# AlimTeleinfoMySensors.net
KiCad netlist of a schematic drawn in EAGLE
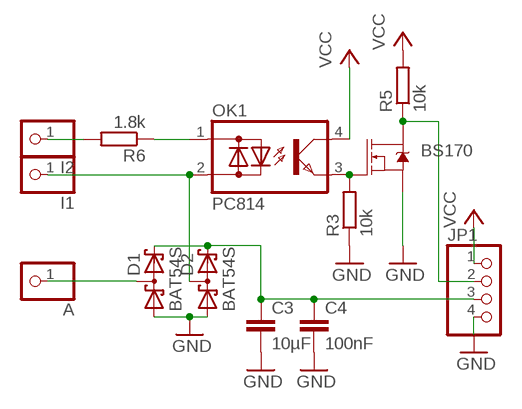
[diagram p0: schematic, sheet 1]

(export (version "E")
  (design (tool "Eeschema 10.0.6"))
  (components
    (comp (ref "A")
      (value "PINHD-1X1")
      (footprint "eagle-import:1X01")
      (libsource (lib "eagle-import") (part "PINHD-1X1"))
    )
    (comp (ref "BS170")
      (value "MOSFET-NCH-BSS138")
      (footprint "eagle-import:SOT23-3")
      (libsource (lib "eagle-import") (part "MOSFET-NCH-BSS138"))
    )
    (comp (ref "C3")
      (value "10µF")
      (footprint "eagle-import:C1210")
      (libsource (lib "eagle-import") (part "C-EUC1210"))
    )
    (comp (ref "C4")
      (value "100nF")
      (footprint "eagle-import:C1206")
      (libsource (lib "eagle-import") (part "C-EUC1206"))
    )
    (comp (ref "D1")
      (value "BAT54S")
      (footprint "eagle-import:SOT23")
      (libsource (lib "eagle-import") (part "BAT54S"))
    )
    (comp (ref "D2")
      (value "BAT54S")
      (footprint "eagle-import:SOT23")
      (libsource (lib "eagle-import") (part "BAT54S"))
    )
    (comp (ref "I1")
      (value "PINHD-1X1")
      (footprint "eagle-import:1X01")
      (libsource (lib "eagle-import") (part "PINHD-1X1"))
    )
    (comp (ref "I2")
      (value "PINHD-1X1")
      (footprint "eagle-import:1X01")
      (libsource (lib "eagle-import") (part "PINHD-1X1"))
    )
    (comp (ref "JP1")
      (value "PINHD-1X4")
      (footprint "eagle-import:1X04")
      (libsource (lib "eagle-import") (part "PINHD-1X4"))
    )
    (comp (ref "OK1")
      (value "PC814")
      (footprint "eagle-import:DIL04")
      (libsource (lib "eagle-import") (part "PC814"))
    )
    (comp (ref "R3")
      (value "10k")
      (footprint "eagle-import:M1206")
      (libsource (lib "eagle-import") (part "R-EU_M1206"))
    )
    (comp (ref "R5")
      (value "10k")
      (footprint "eagle-import:M1206")
      (libsource (lib "eagle-import") (part "R-EU_M1206"))
    )
    (comp (ref "R6")
      (value "1.8k")
      (footprint "eagle-import:M1206")
      (libsource (lib "eagle-import") (part "R-EU_M1206"))
    )
  )
  (nets
    (net (code "1") (name "GND") (class "Default")
      (node (ref "BS170") (pin "2") (pinfunction "S_2") (pintype "bidirectional"))
      (node (ref "C3") (pin "2") (pinfunction "2_2") (pintype "passive"))
      (node (ref "C4") (pin "2") (pinfunction "2_2") (pintype "passive"))
      (node (ref "D1") (pin "1") (pinfunction "A1_1") (pintype "passive"))
      (node (ref "D2") (pin "1") (pinfunction "A1_1") (pintype "passive"))
      (node (ref "JP1") (pin "4") (pinfunction "4_4") (pintype "passive"))
      (node (ref "R3") (pin "1") (pinfunction "1_1") (pintype "passive"))
    )
    (net (code "2") (name "Net-(BS170-D)") (class "Default")
      (node (ref "BS170") (pin "3") (pinfunction "D_3") (pintype "bidirectional"))
      (node (ref "JP1") (pin "2") (pinfunction "2_2") (pintype "passive"))
      (node (ref "R5") (pin "1") (pinfunction "1_1") (pintype "passive"))
    )
    (net (code "3") (name "Net-(BS170-G)") (class "Default")
      (node (ref "BS170") (pin "1") (pinfunction "G_1") (pintype "bidirectional"))
      (node (ref "OK1") (pin "3") (pinfunction "E_3") (pintype "passive"))
      (node (ref "R3") (pin "2") (pinfunction "2_2") (pintype "passive"))
    )
    (net (code "4") (name "Net-(D1-C1A2)") (class "Default")
      (node (ref "A") (pin "1") (pinfunction "1_1") (pintype "passive"))
      (node (ref "D1") (pin "3") (pinfunction "C1A2_3") (pintype "passive"))
    )
    (net (code "5") (name "Net-(D1-C2)") (class "Default")
      (node (ref "C3") (pin "1") (pinfunction "1_1") (pintype "passive"))
      (node (ref "C4") (pin "1") (pinfunction "1_1") (pintype "passive"))
      (node (ref "D1") (pin "2") (pinfunction "C2_2") (pintype "passive"))
      (node (ref "D2") (pin "2") (pinfunction "C2_2") (pintype "passive"))
      (node (ref "JP1") (pin "3") (pinfunction "3_3") (pintype "passive"))
    )
    (net (code "6") (name "Net-(D2-C1A2)") (class "Default")
      (node (ref "D2") (pin "3") (pinfunction "C1A2_3") (pintype "passive"))
      (node (ref "I1") (pin "1") (pinfunction "1_1") (pintype "passive"))
      (node (ref "OK1") (pin "2") (pinfunction "AC2_2") (pintype "passive"))
    )
    (net (code "7") (name "Net-(I2-Pad1)") (class "Default")
      (node (ref "I2") (pin "1") (pinfunction "1_1") (pintype "passive"))
      (node (ref "R6") (pin "2") (pinfunction "2_2") (pintype "passive"))
    )
    (net (code "8") (name "Net-(OK1-AC1)") (class "Default")
      (node (ref "OK1") (pin "1") (pinfunction "AC1_1") (pintype "passive"))
      (node (ref "R6") (pin "1") (pinfunction "1_1") (pintype "passive"))
    )
    (net (code "9") (name "VCC") (class "Default")
      (node (ref "JP1") (pin "1") (pinfunction "1_1") (pintype "passive"))
      (node (ref "OK1") (pin "4") (pinfunction "C_4") (pintype "passive"))
      (node (ref "R5") (pin "2") (pinfunction "2_2") (pintype "passive"))
    )
  )
)
